# Accelerometer.net
KiCad netlist of a schematic drawn in Altium Designer
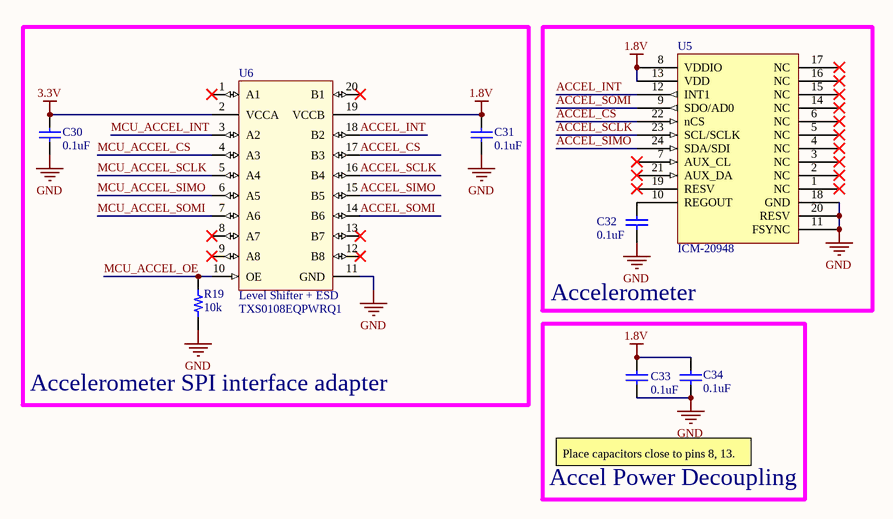
[diagram p0: Accelerometer.SchDoc]

(export (version "E")
  (design (tool "Eeschema 10.0.6"))
  (components
    (comp (ref "C30")
      (value "0.1uF")
      (footprint "Capacitors:C0603")
      (description "0.1uF ceramic capacitor")
      (fields (field (name "MANUFACTURER") "TDK Corporation") (field (name "TOLERANCE") "10%"))
      (libsource (lib "Capacitors") (part "CAP CER 0603 0.1uF 50V C0G 10%"))
    )
    (comp (ref "C31")
      (value "0.1uF")
      (footprint "Capacitors:C0603")
      (description "0.1uF ceramic capacitor")
      (fields (field (name "MANUFACTURER") "TDK Corporation") (field (name "TOLERANCE") "10%"))
      (libsource (lib "Capacitors") (part "CAP CER 0603 0.1uF 50V C0G 10%"))
    )
    (comp (ref "C32")
      (value "0.1uF")
      (footprint "Capacitors:C0603")
      (description "0.1uF ceramic capacitor")
      (fields
        (field (name "MANUFACTURER") "Murata Electronics North America")
        (field (name "TOLERANCE") "10%")
      )
      (libsource (lib "Capacitors") (part "CAP CER 0603 0.1uF 50V C0G 10%"))
    )
    (comp (ref "C33")
      (value "0.1uF")
      (footprint "Capacitors:C0603")
      (description "0.1uF ceramic capacitor")
      (fields
        (field (name "MANUFACTURER") "Murata Electronics North America")
        (field (name "TOLERANCE") "10%")
      )
      (libsource (lib "Capacitors") (part "CAP CER 0603 0.1uF 50V C0G 10%"))
    )
    (comp (ref "C34")
      (value "0.1uF")
      (footprint "Capacitors:C0603")
      (description "0.1uF ceramic capacitor")
      (fields
        (field (name "MANUFACTURER") "Murata Electronics North America")
        (field (name "TOLERANCE") "10%")
      )
      (libsource (lib "Capacitors") (part "CAP CER 0603 0.1uF 50V C0G 10%"))
    )
    (comp (ref "R19")
      (value "10k")
      (footprint "R0603")
      (description "10 kOhms 1% 0.1W Resistor")
      (fields (field (name "MANUFACTURER") "Vishay Dale") (field (name "POWER") "0.1W"))
      (libsource (lib "Resistors") (part "RES 0603 10k 1% 0.1W"))
    )
    (comp (ref "U5")
      (value "ICM-20948")
      (footprint "QFN-24")
      (description "IMU ACCEL/GYRO/COMPI2C/SPI 24QFN")
      (fields (field (name "MANUFACTURER") "TDK InvenSense"))
      (libsource (lib "IC") (part "ICM-20948"))
    )
    (comp (ref "U6")
      (value "Level Shifter + ESD")
      (footprint "PW (R-PDSO-G20)")
      (fields (field (name "MANUFACTURER") "Texas Instruments") (field (name "PART_NUMBER") "TXS0108EQPWRQ1"))
      (libsource (lib "IC") (part "TXS0108EQPWRQ1"))
    )
  )
  (nets
    (net (code "1") (name "/ACCEL_CS") (class "Default")
      (node (ref "U5") (pin "22") (pinfunction "nCS_22") (pintype "input"))
      (node (ref "U6") (pin "17") (pinfunction "B3_17") (pintype "bidirectional"))
    )
    (net (code "2") (name "/ACCEL_INT") (class "Default")
      (node (ref "U5") (pin "12") (pinfunction "INT1_12") (pintype "output"))
      (node (ref "U6") (pin "18") (pinfunction "B2_18") (pintype "bidirectional"))
    )
    (net (code "3") (name "/ACCEL_SCLK") (class "Default")
      (node (ref "U5") (pin "23") (pinfunction "SCL/SCLK_23") (pintype "input"))
      (node (ref "U6") (pin "16") (pinfunction "B4_16") (pintype "bidirectional"))
    )
    (net (code "4") (name "/ACCEL_SIMO") (class "Default")
      (node (ref "U5") (pin "24") (pinfunction "SDA/SDI_24") (pintype "input"))
      (node (ref "U6") (pin "15") (pinfunction "B5_15") (pintype "bidirectional"))
    )
    (net (code "5") (name "/ACCEL_SOMI") (class "Default")
      (node (ref "U5") (pin "9") (pinfunction "SDO/AD0_9") (pintype "output"))
      (node (ref "U6") (pin "14") (pinfunction "B6_14") (pintype "bidirectional"))
    )
    (net (code "6") (name "/MCU_ACCEL_CS") (class "Default")
      (node (ref "U6") (pin "4") (pinfunction "A3_4") (pintype "bidirectional"))
    )
    (net (code "7") (name "/MCU_ACCEL_INT") (class "Default")
      (node (ref "U6") (pin "3") (pinfunction "A2_3") (pintype "bidirectional"))
    )
    (net (code "8") (name "/MCU_ACCEL_OE") (class "Default")
      (node (ref "R19") (pin "2") (pinfunction "2_2") (pintype "passive"))
      (node (ref "U6") (pin "10") (pinfunction "OE_10") (pintype "input"))
    )
    (net (code "9") (name "/MCU_ACCEL_SCLK") (class "Default")
      (node (ref "U6") (pin "5") (pinfunction "A4_5") (pintype "bidirectional"))
    )
    (net (code "10") (name "/MCU_ACCEL_SIMO") (class "Default")
      (node (ref "U6") (pin "6") (pinfunction "A5_6") (pintype "bidirectional"))
    )
    (net (code "11") (name "/MCU_ACCEL_SOMI") (class "Default")
      (node (ref "U6") (pin "7") (pinfunction "A6_7") (pintype "bidirectional"))
    )
    (net (code "12") (name "1.8V") (class "Default")
      (node (ref "C31") (pin "2") (pinfunction "2_2") (pintype "passive"))
      (node (ref "C33") (pin "2") (pinfunction "2_2") (pintype "passive"))
      (node (ref "C34") (pin "2") (pinfunction "2_2") (pintype "passive"))
      (node (ref "U5") (pin "13") (pinfunction "VDD_13") (pintype "power_in"))
      (node (ref "U5") (pin "8") (pinfunction "VDDIO_8") (pintype "power_in"))
      (node (ref "U6") (pin "19") (pinfunction "VCCB_19") (pintype "power_in"))
    )
    (net (code "13") (name "3.3V") (class "Default")
      (node (ref "C30") (pin "2") (pinfunction "2_2") (pintype "passive"))
      (node (ref "U6") (pin "2") (pinfunction "VCCA_2") (pintype "power_in"))
    )
    (net (code "14") (name "GND") (class "Default")
      (node (ref "C30") (pin "1") (pinfunction "1_1") (pintype "passive"))
      (node (ref "C31") (pin "1") (pinfunction "1_1") (pintype "passive"))
      (node (ref "C32") (pin "1") (pinfunction "1_1") (pintype "passive"))
      (node (ref "C33") (pin "1") (pinfunction "1_1") (pintype "passive"))
      (node (ref "C34") (pin "1") (pinfunction "1_1") (pintype "passive"))
      (node (ref "R19") (pin "1") (pinfunction "1_1") (pintype "passive"))
      (node (ref "U5") (pin "11") (pinfunction "FSYNC_11") (pintype "power_in"))
      (node (ref "U5") (pin "18") (pinfunction "GND_18") (pintype "power_in"))
      (node (ref "U5") (pin "20") (pinfunction "RESV_20") (pintype "power_in"))
      (node (ref "U6") (pin "11") (pinfunction "GND_11") (pintype "power_in"))
    )
    (net (code "15") (name "Net-(U5-REGOUT)") (class "Default")
      (node (ref "C32") (pin "2") (pinfunction "2_2") (pintype "passive"))
      (node (ref "U5") (pin "10") (pinfunction "REGOUT_10") (pintype "passive"))
    )
    (net (code "16") (name "unconnected-(U5-AUX_CL-Pad7)") (class "Default")
      (node (ref "U5") (pin "7") (pinfunction "AUX_CL_7") (pintype "input+no_connect"))
    )
    (net (code "17") (name "unconnected-(U5-AUX_DA-Pad21)") (class "Default")
      (node (ref "U5") (pin "21") (pinfunction "AUX_DA_21") (pintype "input+no_connect"))
    )
    (net (code "18") (name "unconnected-(U5-NC-Pad1)") (class "Default")
      (node (ref "U5") (pin "1") (pinfunction "NC_1") (pintype "passive+no_connect"))
    )
    (net (code "19") (name "unconnected-(U5-NC-Pad2)") (class "Default")
      (node (ref "U5") (pin "2") (pinfunction "NC_2") (pintype "passive+no_connect"))
    )
    (net (code "20") (name "unconnected-(U5-NC-Pad3)") (class "Default")
      (node (ref "U5") (pin "3") (pinfunction "NC_3") (pintype "passive+no_connect"))
    )
    (net (code "21") (name "unconnected-(U5-NC-Pad4)") (class "Default")
      (node (ref "U5") (pin "4") (pinfunction "NC_4") (pintype "passive+no_connect"))
    )
    (net (code "22") (name "unconnected-(U5-NC-Pad5)") (class "Default")
      (node (ref "U5") (pin "5") (pinfunction "NC_5") (pintype "passive+no_connect"))
    )
    (net (code "23") (name "unconnected-(U5-NC-Pad6)") (class "Default")
      (node (ref "U5") (pin "6") (pinfunction "NC_6") (pintype "passive+no_connect"))
    )
    (net (code "24") (name "unconnected-(U5-NC-Pad14)") (class "Default")
      (node (ref "U5") (pin "14") (pinfunction "NC_14") (pintype "passive+no_connect"))
    )
    (net (code "25") (name "unconnected-(U5-NC-Pad15)") (class "Default")
      (node (ref "U5") (pin "15") (pinfunction "NC_15") (pintype "passive+no_connect"))
    )
    (net (code "26") (name "unconnected-(U5-NC-Pad16)") (class "Default")
      (node (ref "U5") (pin "16") (pinfunction "NC_16") (pintype "passive+no_connect"))
    )
    (net (code "27") (name "unconnected-(U5-NC-Pad17)") (class "Default")
      (node (ref "U5") (pin "17") (pinfunction "NC_17") (pintype "passive+no_connect"))
    )
    (net (code "28") (name "unconnected-(U5-RESV-Pad19)") (class "Default")
      (node (ref "U5") (pin "19") (pinfunction "RESV_19") (pintype "passive+no_connect"))
    )
    (net (code "29") (name "unconnected-(U6-A1-Pad1)") (class "Default")
      (node (ref "U6") (pin "1") (pinfunction "A1_1") (pintype "bidirectional+no_connect"))
    )
    (net (code "30") (name "unconnected-(U6-A7-Pad8)") (class "Default")
      (node (ref "U6") (pin "8") (pinfunction "A7_8") (pintype "bidirectional+no_connect"))
    )
    (net (code "31") (name "unconnected-(U6-A8-Pad9)") (class "Default")
      (node (ref "U6") (pin "9") (pinfunction "A8_9") (pintype "bidirectional+no_connect"))
    )
    (net (code "32") (name "unconnected-(U6-B1-Pad20)") (class "Default")
      (node (ref "U6") (pin "20") (pinfunction "B1_20") (pintype "bidirectional+no_connect"))
    )
    (net (code "33") (name "unconnected-(U6-B7-Pad13)") (class "Default")
      (node (ref "U6") (pin "13") (pinfunction "B7_13") (pintype "bidirectional+no_connect"))
    )
    (net (code "34") (name "unconnected-(U6-B8-Pad12)") (class "Default")
      (node (ref "U6") (pin "12") (pinfunction "B8_12") (pintype "bidirectional+no_connect"))
    )
  )
)
